# bike-blinky.net
KiCad netlist of a schematic drawn in EAGLE
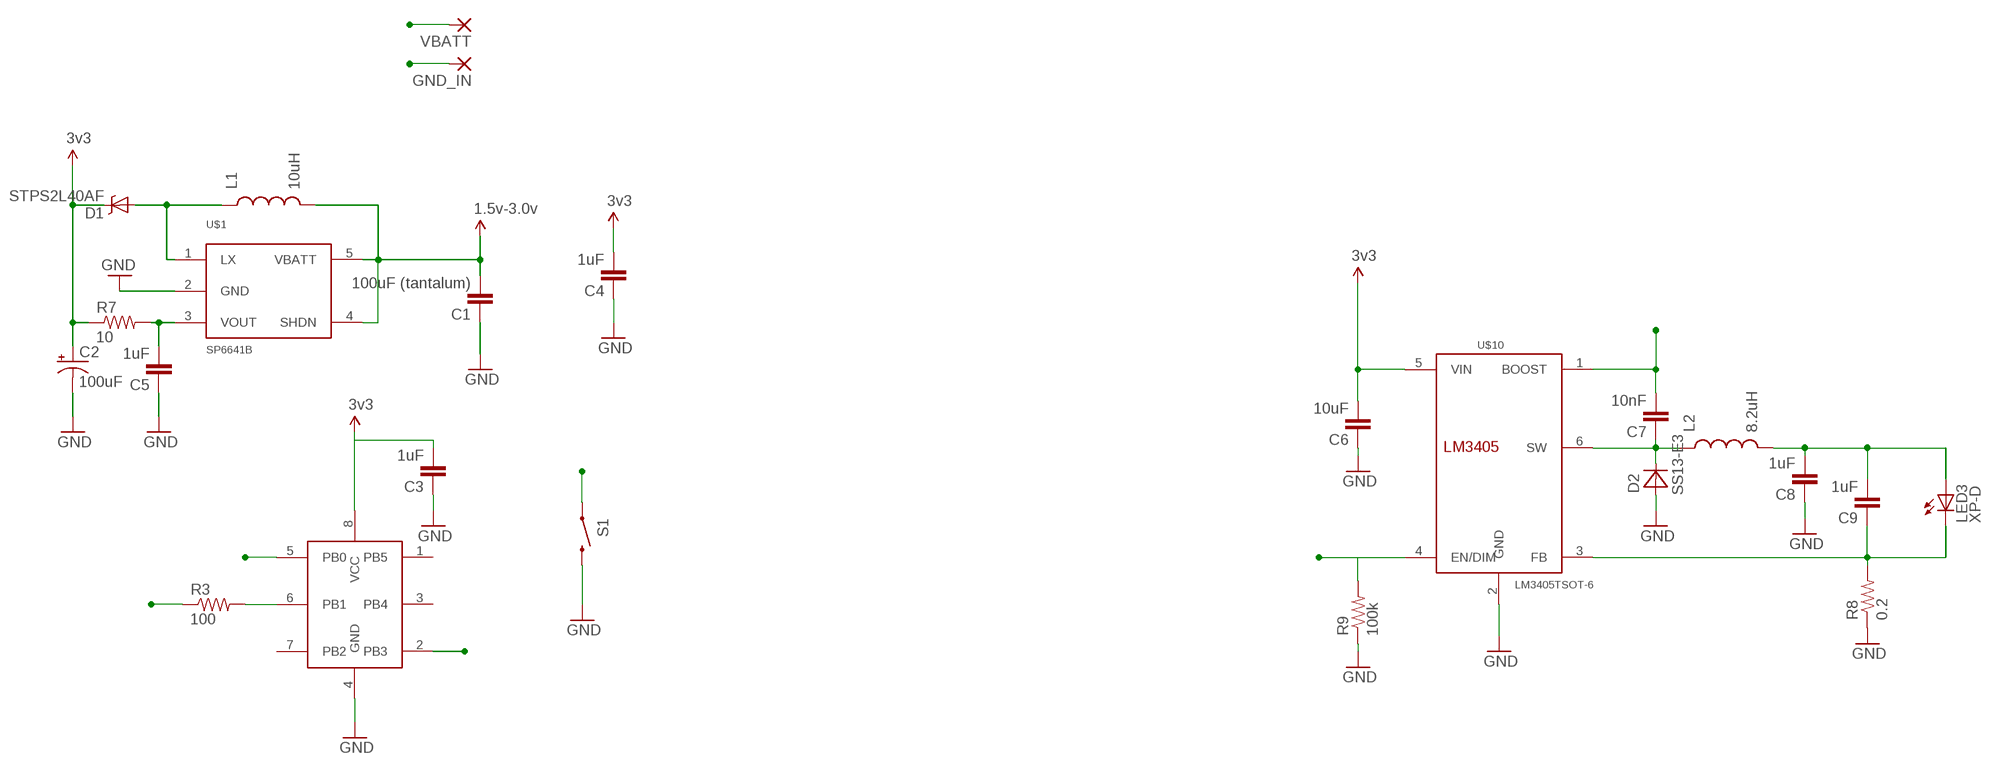
[diagram p0: schematic, sheet 1]

(export (version "E")
  (design (tool "Eeschema 10.0.6"))
  (components
    (comp (ref "C1")
      (value "100uF (tantalum)")
      (footprint "eagle-import:1206")
      (libsource (lib "eagle-import") (part "CAP1206"))
    )
    (comp (ref "C2")
      (value "100uF")
      (footprint "eagle-import:PANASONIC_C")
      (libsource (lib "eagle-import") (part "CAP_POLC"))
    )
    (comp (ref "C3")
      (value "1uF")
      (footprint "eagle-import:0603-CAP")
      (libsource (lib "eagle-import") (part "CAP0603-CAP"))
    )
    (comp (ref "C4")
      (value "1uF")
      (footprint "eagle-import:0603-CAP")
      (libsource (lib "eagle-import") (part "CAP0603-CAP"))
    )
    (comp (ref "C5")
      (value "1uF")
      (footprint "eagle-import:0603-CAP")
      (libsource (lib "eagle-import") (part "CAP0603-CAP"))
    )
    (comp (ref "C6")
      (value "10uF")
      (footprint "eagle-import:1206")
      (libsource (lib "eagle-import") (part "SparkFun-Capacitors_CAP1206"))
    )
    (comp (ref "C7")
      (value "10nF")
      (footprint "eagle-import:0603-CAP")
      (libsource (lib "eagle-import") (part "SparkFun-Capacitors_CAP0603-CAP"))
    )
    (comp (ref "C8")
      (value "1uF")
      (footprint "eagle-import:0603-CAP")
      (libsource (lib "eagle-import") (part "SparkFun-Capacitors_CAP0603-CAP"))
    )
    (comp (ref "C9")
      (value "1uF")
      (footprint "eagle-import:0603-CAP")
      (libsource (lib "eagle-import") (part "SparkFun-Capacitors_CAP0603-CAP"))
    )
    (comp (ref "D1")
      (value "STPS2L40AF")
      (footprint "eagle-import:SMA-DIODE")
      (libsource (lib "eagle-import") (part "MBRA140"))
    )
    (comp (ref "D2")
      (value "SS13-E3")
      (footprint "eagle-import:SMA")
      (libsource (lib "eagle-import") (part "MBRA340T3"))
    )
    (comp (ref "GND_IN")
      (value "WIREPAD2,54/1,0")
      (footprint "eagle-import:2,54_1,0")
      (libsource (lib "eagle-import") (part "WIREPAD2,54/1,0"))
    )
    (comp (ref "L1")
      (value "10uH")
      (footprint "eagle-import:1007")
      (libsource (lib "eagle-import") (part "INDUCTOR1007"))
    )
    (comp (ref "L2")
      (value "8.2uH")
      (footprint "eagle-import:1210")
      (libsource (lib "eagle-import") (part "INDUCTOR1210"))
    )
    (comp (ref "LED3")
      (value "XP-D")
      (footprint "eagle-import:XB-D-REV1")
      (libsource (lib "eagle-import") (part "XLAMP-XB-D-LED"))
    )
    (comp (ref "R3")
      (value "100")
      (footprint "eagle-import:0603-RES")
      (libsource (lib "eagle-import") (part "RESISTOR0603-RES"))
    )
    (comp (ref "R7")
      (value "10")
      (footprint "eagle-import:0603-RES")
      (libsource (lib "eagle-import") (part "SparkFun-Passives_RESISTOR0603-RES"))
    )
    (comp (ref "R8")
      (value "0.2")
      (footprint "eagle-import:R2010")
      (libsource (lib "eagle-import") (part "SparkFun-Passives_RESISTOR2010"))
    )
    (comp (ref "R9")
      (value "100k")
      (footprint "eagle-import:0603-RES")
      (libsource (lib "eagle-import") (part "SparkFun-Passives_RESISTOR0603-RES"))
    )
    (comp (ref "S1")
      (value "SWITCH-MOMENTARY-2SMD-2")
      (footprint "eagle-import:TACTILE_SWITCH_SMD-2")
      (libsource (lib "eagle-import") (part "SWITCH-MOMENTARY-2SMD-2"))
    )
    (comp (ref "U$1")
      (value "SP6641B")
      (footprint "eagle-import:SOT23-5")
      (libsource (lib "eagle-import") (part "SP6641SP6641A/B"))
    )
    (comp (ref "U$2")
      (value "ATTINY13")
      (footprint "eagle-import:WSOIC-8")
      (libsource (lib "eagle-import") (part "ATTINY13"))
    )
    (comp (ref "U$10")
      (value "LM3405TSOT-6")
      (footprint "eagle-import:TSOT-6")
      (libsource (lib "eagle-import") (part "LM3405TSOT-6"))
    )
    (comp (ref "VBATT")
      (value "WIREPAD2,54/1,0")
      (footprint "eagle-import:2,54_1,0")
      (libsource (lib "eagle-import") (part "WIREPAD2,54/1,0"))
    )
  )
  (nets
    (net (code "1") (name "/ENABLE") (class "Default")
      (node (ref "C7") (pin "2") (pinfunction "2_2") (pintype "passive"))
      (node (ref "U$10") (pin "1") (pinfunction "BOOST_1") (pintype "bidirectional"))
      (node (ref "U$2") (pin "2") (pinfunction "PB3_2") (pintype "bidirectional"))
    )
    (net (code "2") (name "/RED") (class "Default")
      (node (ref "R3") (pin "1") (pinfunction "1_1") (pintype "passive"))
      (node (ref "R9") (pin "2") (pinfunction "2_2") (pintype "passive"))
      (node (ref "U$10") (pin "4") (pinfunction "EN/DIM_4") (pintype "bidirectional"))
    )
    (net (code "3") (name "/SW") (class "Default")
      (node (ref "S1") (pin "2") (pinfunction "1_2") (pintype "passive"))
      (node (ref "U$2") (pin "5") (pinfunction "PB0_5") (pintype "bidirectional"))
    )
    (net (code "4") (name "1.5v-3.0v") (class "Default")
      (node (ref "C1") (pin "2") (pinfunction "2_2") (pintype "passive"))
      (node (ref "L1") (pin "2") (pinfunction "2_2") (pintype "passive"))
      (node (ref "U$1") (pin "4") (pinfunction "SHDN_4") (pintype "bidirectional"))
      (node (ref "U$1") (pin "5") (pinfunction "VBATT_5") (pintype "bidirectional"))
      (node (ref "VBATT") (pin "1") (pinfunction "P_1") (pintype "passive"))
    )
    (net (code "5") (name "3v3") (class "Default")
      (node (ref "C2") (pin "+") (pinfunction "+_+") (pintype "passive"))
      (node (ref "C3") (pin "2") (pinfunction "2_2") (pintype "passive"))
      (node (ref "C4") (pin "2") (pinfunction "2_2") (pintype "passive"))
      (node (ref "C6") (pin "2") (pinfunction "2_2") (pintype "passive"))
      (node (ref "D1") (pin "C") (pinfunction "C_C") (pintype "passive"))
      (node (ref "R7") (pin "1") (pinfunction "1_1") (pintype "passive"))
      (node (ref "U$10") (pin "5") (pinfunction "VIN_5") (pintype "bidirectional"))
      (node (ref "U$2") (pin "8") (pinfunction "VCC_8") (pintype "bidirectional"))
    )
    (net (code "6") (name "GND") (class "Default")
      (node (ref "C1") (pin "1") (pinfunction "1_1") (pintype "passive"))
      (node (ref "C2") (pin "-") (pinfunction "-_-") (pintype "passive"))
      (node (ref "C3") (pin "1") (pinfunction "1_1") (pintype "passive"))
      (node (ref "C4") (pin "1") (pinfunction "1_1") (pintype "passive"))
      (node (ref "C5") (pin "1") (pinfunction "1_1") (pintype "passive"))
      (node (ref "C6") (pin "1") (pinfunction "1_1") (pintype "passive"))
      (node (ref "C8") (pin "1") (pinfunction "1_1") (pintype "passive"))
      (node (ref "D2") (pin "A") (pinfunction "A_A") (pintype "passive"))
      (node (ref "GND_IN") (pin "1") (pinfunction "P_1") (pintype "passive"))
      (node (ref "R8") (pin "1") (pinfunction "1_1") (pintype "passive"))
      (node (ref "R9") (pin "1") (pinfunction "1_1") (pintype "passive"))
      (node (ref "S1") (pin "1") (pinfunction "2_1") (pintype "passive"))
      (node (ref "U$1") (pin "2") (pinfunction "GND_2") (pintype "bidirectional"))
      (node (ref "U$10") (pin "2") (pinfunction "GND_2") (pintype "bidirectional"))
      (node (ref "U$2") (pin "4") (pinfunction "GND_4") (pintype "bidirectional"))
    )
    (net (code "7") (name "Net-(C8-Pad2)") (class "Default")
      (node (ref "C8") (pin "2") (pinfunction "2_2") (pintype "passive"))
      (node (ref "C9") (pin "2") (pinfunction "2_2") (pintype "passive"))
      (node (ref "L2") (pin "2") (pinfunction "2_2") (pintype "passive"))
      (node (ref "LED3") (pin "A") (pinfunction "A_A") (pintype "passive"))
    )
    (net (code "8") (name "Net-(U$1-LX)") (class "Default")
      (node (ref "D1") (pin "A") (pinfunction "A_A") (pintype "passive"))
      (node (ref "L1") (pin "1") (pinfunction "1_1") (pintype "passive"))
      (node (ref "U$1") (pin "1") (pinfunction "LX_1") (pintype "bidirectional"))
    )
    (net (code "9") (name "Net-(U$1-VOUT)") (class "Default")
      (node (ref "C5") (pin "2") (pinfunction "2_2") (pintype "passive"))
      (node (ref "R7") (pin "2") (pinfunction "2_2") (pintype "passive"))
      (node (ref "U$1") (pin "3") (pinfunction "VOUT_3") (pintype "bidirectional"))
    )
    (net (code "10") (name "Net-(U$2-PB1)") (class "Default")
      (node (ref "R3") (pin "2") (pinfunction "2_2") (pintype "passive"))
      (node (ref "U$2") (pin "6") (pinfunction "PB1_6") (pintype "bidirectional"))
    )
    (net (code "11") (name "Net-(U$10-FB)") (class "Default")
      (node (ref "C9") (pin "1") (pinfunction "1_1") (pintype "passive"))
      (node (ref "LED3") (pin "C") (pinfunction "C_C") (pintype "passive"))
      (node (ref "R8") (pin "2") (pinfunction "2_2") (pintype "passive"))
      (node (ref "U$10") (pin "3") (pinfunction "FB_3") (pintype "bidirectional"))
    )
    (net (code "12") (name "Net-(U$10-SW)") (class "Default")
      (node (ref "C7") (pin "1") (pinfunction "1_1") (pintype "passive"))
      (node (ref "D2") (pin "C") (pinfunction "C_C") (pintype "passive"))
      (node (ref "L2") (pin "1") (pinfunction "1_1") (pintype "passive"))
      (node (ref "U$10") (pin "6") (pinfunction "SW_6") (pintype "bidirectional"))
    )
    (net (code "13") (name "unconnected-(U$2-PB2-Pad7)") (class "Default")
      (node (ref "U$2") (pin "7") (pinfunction "PB2_7") (pintype "bidirectional"))
    )
    (net (code "14") (name "unconnected-(U$2-PB4-Pad3)") (class "Default")
      (node (ref "U$2") (pin "3") (pinfunction "PB4_3") (pintype "bidirectional"))
    )
    (net (code "15") (name "unconnected-(U$2-PB5-Pad1)") (class "Default")
      (node (ref "U$2") (pin "1") (pinfunction "PB5_1") (pintype "bidirectional"))
    )
  )
)
